# Moz_Mo_1_1.net
KiCad netlist of a schematic drawn in EAGLE
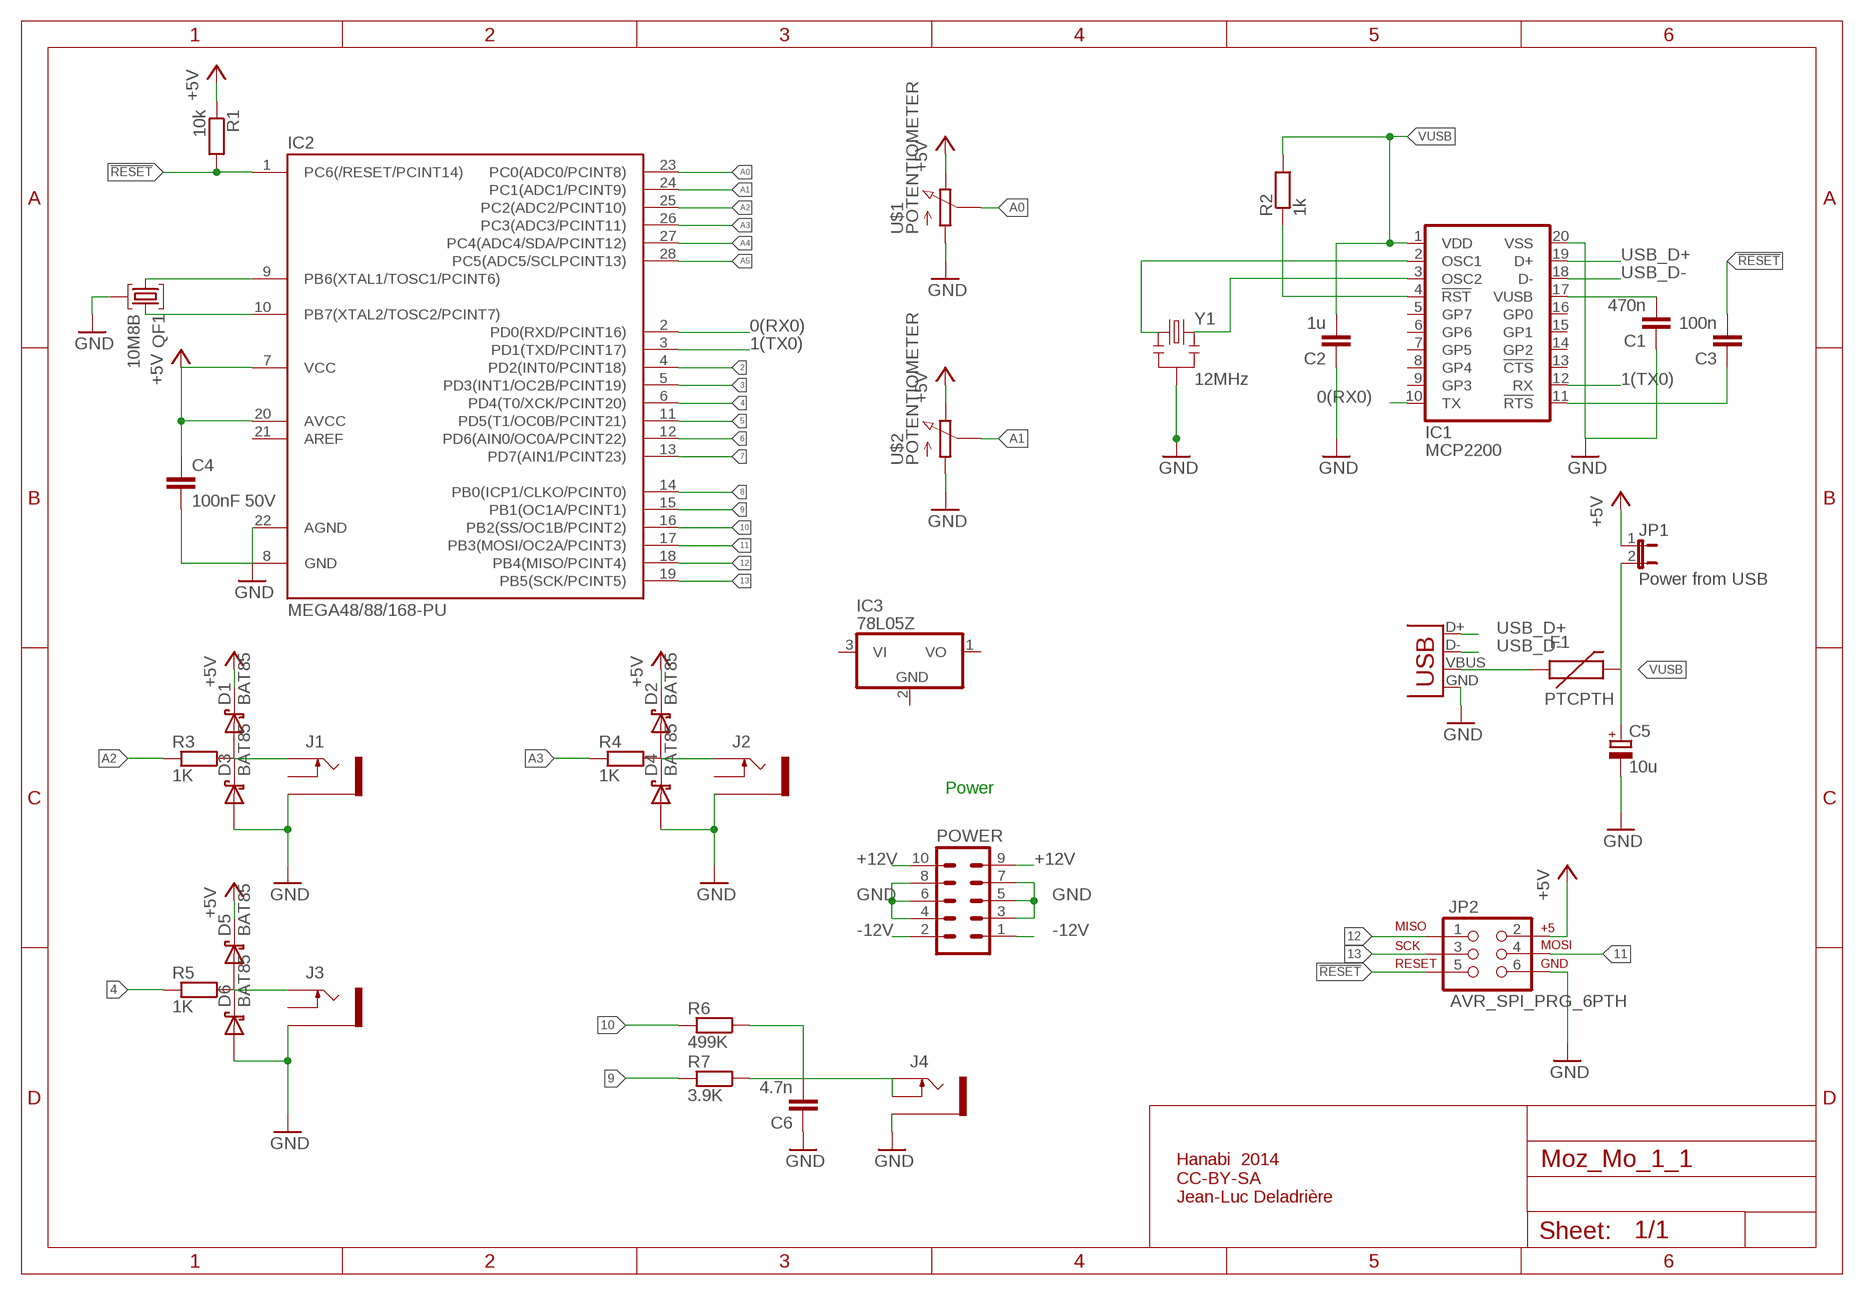
[diagram p0: schematic, sheet 1]

(export (version "E")
  (design (tool "Eeschema 10.0.6"))
  (components
    (comp (ref "C1")
      (value "470n")
      (footprint "eagle-import:CAP-PTH-SMALL")
      (libsource (lib "eagle-import") (part "CAPPTH"))
    )
    (comp (ref "C2")
      (value "1u")
      (footprint "eagle-import:CAP-PTH-5MM")
      (libsource (lib "eagle-import") (part "CAPPTH1"))
    )
    (comp (ref "C3")
      (value "100n")
      (footprint "eagle-import:CAP-PTH-SMALL")
      (libsource (lib "eagle-import") (part "CAPPTH"))
    )
    (comp (ref "C4")
      (value "100nF 50V")
      (footprint "eagle-import:C025-025X050")
      (libsource (lib "eagle-import") (part "C-EU025-025X050"))
    )
    (comp (ref "C5")
      (value "10u")
      (footprint "eagle-import:E2,5-7")
      (libsource (lib "eagle-import") (part "CPOL-EUE2.5-7"))
    )
    (comp (ref "C6")
      (value "4.7n")
      (footprint "eagle-import:CAP-PTH-SMALL")
      (libsource (lib "eagle-import") (part "CAPPTH"))
    )
    (comp (ref "D1")
      (value "BAT85")
      (footprint "eagle-import:DIODE-TH-0.4")
      (libsource (lib "eagle-import") (part "DIODE-SCHOTTKY"))
    )
    (comp (ref "D2")
      (value "BAT85")
      (footprint "eagle-import:DIODE-TH-0.4")
      (libsource (lib "eagle-import") (part "DIODE-SCHOTTKY"))
    )
    (comp (ref "D3")
      (value "BAT85")
      (footprint "eagle-import:DIODE-TH-0.4")
      (libsource (lib "eagle-import") (part "DIODE-SCHOTTKY"))
    )
    (comp (ref "D4")
      (value "BAT85")
      (footprint "eagle-import:DIODE-TH-0.4")
      (libsource (lib "eagle-import") (part "DIODE-SCHOTTKY"))
    )
    (comp (ref "D5")
      (value "BAT85")
      (footprint "eagle-import:DIODE-TH-0.4")
      (libsource (lib "eagle-import") (part "DIODE-SCHOTTKY"))
    )
    (comp (ref "D6")
      (value "BAT85")
      (footprint "eagle-import:DIODE-TH-0.4")
      (libsource (lib "eagle-import") (part "DIODE-SCHOTTKY"))
    )
    (comp (ref "F1")
      (value "PTCPTH")
      (footprint "eagle-import:PTC")
      (libsource (lib "eagle-import") (part "PTCPTH"))
    )
    (comp (ref "IC1")
      (value "MCP2200")
      (footprint "eagle-import:SO20")
      (libsource (lib "eagle-import") (part "MCP2200"))
    )
    (comp (ref "IC2")
      (value "MEGA48/88/168-PU")
      (footprint "eagle-import:DIL28-3")
      (libsource (lib "eagle-import") (part "MEGA48/88/168-PU"))
    )
    (comp (ref "IC3")
      (value "78L05Z")
      (footprint "eagle-import:TO92")
      (libsource (lib "eagle-import") (part "78ZL05"))
    )
    (comp (ref "J1")
      (value "1503_12")
      (footprint "eagle-import:1503_12")
      (libsource (lib "eagle-import") (part "1503_12"))
    )
    (comp (ref "J2")
      (value "1503_12")
      (footprint "eagle-import:1503_12")
      (libsource (lib "eagle-import") (part "1503_12"))
    )
    (comp (ref "J3")
      (value "1503_12")
      (footprint "eagle-import:1503_12")
      (libsource (lib "eagle-import") (part "1503_12"))
    )
    (comp (ref "J4")
      (value "1503_12")
      (footprint "eagle-import:1503_12")
      (libsource (lib "eagle-import") (part "1503_12"))
    )
    (comp (ref "JP1")
      (value "Power from USB")
      (footprint "eagle-import:JP1")
      (libsource (lib "eagle-import") (part "JP1E"))
    )
    (comp (ref "JP2")
      (value "AVR_SPI_PRG_6PTH")
      (footprint "eagle-import:2X3")
      (libsource (lib "eagle-import") (part "AVR_SPI_PRG_6PTH"))
    )
    (comp (ref "POWER")
      (value "10_PIN_HEADER")
      (footprint "eagle-import:MA05-2")
      (libsource (lib "eagle-import") (part "10_PIN_HEADER"))
    )
    (comp (ref "QF1")
      (value "10M8B")
      (footprint "eagle-import:HC49U")
      (fields (field (name "OC_FARNELL") "1448129"))
      (libsource (lib "eagle-import") (part "10MB8"))
    )
    (comp (ref "R1")
      (value "10k")
      (footprint "eagle-import:RES-AXIAL-0.4")
      (libsource (lib "eagle-import") (part "RESISTOR"))
    )
    (comp (ref "R2")
      (value "1k")
      (footprint "eagle-import:RES-AXIAL-0.4")
      (libsource (lib "eagle-import") (part "RESISTOR"))
    )
    (comp (ref "R3")
      (value "1K")
      (footprint "eagle-import:RES-AXIAL-0.4")
      (libsource (lib "eagle-import") (part "RESISTOR"))
    )
    (comp (ref "R4")
      (value "1K")
      (footprint "eagle-import:RES-AXIAL-0.4")
      (libsource (lib "eagle-import") (part "RESISTOR"))
    )
    (comp (ref "R5")
      (value "1K")
      (footprint "eagle-import:RES-AXIAL-0.4")
      (libsource (lib "eagle-import") (part "RESISTOR"))
    )
    (comp (ref "R6")
      (value "499K")
      (footprint "eagle-import:RES-AXIAL-0.4")
      (libsource (lib "eagle-import") (part "RESISTOR"))
    )
    (comp (ref "R7")
      (value "3.9K")
      (footprint "eagle-import:RES-AXIAL-0.4")
      (libsource (lib "eagle-import") (part "RESISTOR"))
    )
    (comp (ref "U$1")
      (value "POTENTIOMETER")
      (footprint "eagle-import:POTENTIOMETER")
      (libsource (lib "eagle-import") (part "POTENTIOMETER"))
    )
    (comp (ref "U$2")
      (value "POTENTIOMETER")
      (footprint "eagle-import:POTENTIOMETER")
      (libsource (lib "eagle-import") (part "POTENTIOMETER"))
    )
    (comp (ref "X1")
      (value "USB")
      (footprint "eagle-import:USB-B-PTH")
      (libsource (lib "eagle-import") (part "USBPTH"))
    )
    (comp (ref "Y1")
      (value "12MHz")
      (footprint "eagle-import:HC49U-V-RESONATOR")
      (libsource (lib "eagle-import") (part "CRYSTAL-RESONATOR"))
    )
  )
  (nets
    (net (code "1") (name "+5V") (class "Default")
      (node (ref "C4") (pin "1") (pinfunction "1_1") (pintype "passive"))
      (node (ref "D1") (pin "C") (pinfunction "C_C") (pintype "passive"))
      (node (ref "D2") (pin "C") (pinfunction "C_C") (pintype "passive"))
      (node (ref "D5") (pin "C") (pinfunction "C_C") (pintype "passive"))
      (node (ref "IC2") (pin "20") (pinfunction "AVCC_20") (pintype "passive"))
      (node (ref "IC2") (pin "7") (pinfunction "VCC_7") (pintype "power_in"))
      (node (ref "JP1") (pin "1") (pinfunction "1_1") (pintype "passive"))
      (node (ref "JP2") (pin "2") (pinfunction "2_2") (pintype "passive"))
      (node (ref "R1") (pin "P$1") (pinfunction "1_P$1") (pintype "passive"))
      (node (ref "U$1") (pin "P$1") (pinfunction "E_P$1") (pintype "passive"))
      (node (ref "U$2") (pin "P$1") (pinfunction "E_P$1") (pintype "passive"))
    )
    (net (code "2") (name "/+12V") (class "Default")
      (node (ref "POWER") (pin "10") (pinfunction "10_10") (pintype "passive"))
      (node (ref "POWER") (pin "9") (pinfunction "9_9") (pintype "passive"))
    )
    (net (code "3") (name "/-12V") (class "Default")
      (node (ref "POWER") (pin "1") (pinfunction "1_1") (pintype "passive"))
      (node (ref "POWER") (pin "2") (pinfunction "2_2") (pintype "passive"))
    )
    (net (code "4") (name "/0(RX0)") (class "Default")
      (node (ref "IC1") (pin "10") (pinfunction "TX_10") (pintype "bidirectional"))
      (node (ref "IC2") (pin "2") (pinfunction "PD0(RXD/PCINT16)_2") (pintype "bidirectional"))
    )
    (net (code "5") (name "/1(TX0)") (class "Default")
      (node (ref "IC1") (pin "12") (pinfunction "RX_12") (pintype "bidirectional"))
      (node (ref "IC2") (pin "3") (pinfunction "PD1(TXD/PCINT17)_3") (pintype "bidirectional"))
    )
    (net (code "6") (name "/USB_D+") (class "Default")
      (node (ref "IC1") (pin "19") (pinfunction "D+_19") (pintype "bidirectional"))
      (node (ref "X1") (pin "D+") (pinfunction "D+_D+") (pintype "bidirectional"))
    )
    (net (code "7") (name "/USB_D-") (class "Default")
      (node (ref "IC1") (pin "18") (pinfunction "D-_18") (pintype "bidirectional"))
      (node (ref "X1") (pin "D-") (pinfunction "D-_D-") (pintype "bidirectional"))
    )
    (net (code "8") (name "/~{RESET}") (class "Default")
      (node (ref "C3") (pin "2") (pinfunction "2_2") (pintype "passive"))
      (node (ref "IC2") (pin "1") (pinfunction "PC6(/RESET/PCINT14)_1") (pintype "bidirectional"))
      (node (ref "JP2") (pin "5") (pinfunction "5_5") (pintype "passive"))
      (node (ref "R1") (pin "P$2") (pinfunction "2_P$2") (pintype "passive"))
    )
    (net (code "9") (name "2") (class "Default")
      (node (ref "IC2") (pin "4") (pinfunction "PD2(INT0/PCINT18)_4") (pintype "bidirectional"))
    )
    (net (code "10") (name "3") (class "Default")
      (node (ref "IC2") (pin "5") (pinfunction "PD3(INT1/OC2B/PCINT19)_5") (pintype "bidirectional"))
    )
    (net (code "11") (name "4") (class "Default")
      (node (ref "IC2") (pin "6") (pinfunction "PD4(T0/XCK/PCINT20)_6") (pintype "bidirectional"))
      (node (ref "R5") (pin "P$1") (pinfunction "1_P$1") (pintype "passive"))
    )
    (net (code "12") (name "5") (class "Default")
      (node (ref "IC2") (pin "11") (pinfunction "PD5(T1/OC0B/PCINT21)_11") (pintype "bidirectional"))
    )
    (net (code "13") (name "6") (class "Default")
      (node (ref "IC2") (pin "12") (pinfunction "PD6(AIN0/OC0A/PCINT22)_12") (pintype "bidirectional"))
    )
    (net (code "14") (name "7") (class "Default")
      (node (ref "IC2") (pin "13") (pinfunction "PD7(AIN1/PCINT23)_13") (pintype "bidirectional"))
    )
    (net (code "15") (name "8") (class "Default")
      (node (ref "IC2") (pin "14") (pinfunction "PB0(ICP1/CLKO/PCINT0)_14") (pintype "bidirectional"))
    )
    (net (code "16") (name "9") (class "Default")
      (node (ref "IC2") (pin "15") (pinfunction "PB1(OC1A/PCINT1)_15") (pintype "bidirectional"))
      (node (ref "R7") (pin "P$1") (pinfunction "1_P$1") (pintype "passive"))
    )
    (net (code "17") (name "10") (class "Default")
      (node (ref "IC2") (pin "16") (pinfunction "PB2(SS/OC1B/PCINT2)_16") (pintype "bidirectional"))
      (node (ref "R6") (pin "P$1") (pinfunction "1_P$1") (pintype "passive"))
    )
    (net (code "18") (name "11") (class "Default")
      (node (ref "IC2") (pin "17") (pinfunction "PB3(MOSI/OC2A/PCINT3)_17") (pintype "bidirectional"))
      (node (ref "JP2") (pin "4") (pinfunction "4_4") (pintype "passive"))
    )
    (net (code "19") (name "12") (class "Default")
      (node (ref "IC2") (pin "18") (pinfunction "PB4(MISO/PCINT4)_18") (pintype "bidirectional"))
      (node (ref "JP2") (pin "1") (pinfunction "1_1") (pintype "passive"))
    )
    (net (code "20") (name "13") (class "Default")
      (node (ref "IC2") (pin "19") (pinfunction "PB5(SCK/PCINT5)_19") (pintype "bidirectional"))
      (node (ref "JP2") (pin "3") (pinfunction "3_3") (pintype "passive"))
    )
    (net (code "21") (name "A0") (class "Default")
      (node (ref "IC2") (pin "23") (pinfunction "PC0(ADC0/PCINT8)_23") (pintype "bidirectional"))
      (node (ref "U$1") (pin "P$2") (pinfunction "S_P$2") (pintype "passive"))
    )
    (net (code "22") (name "A1") (class "Default")
      (node (ref "IC2") (pin "24") (pinfunction "PC1(ADC1/PCINT9)_24") (pintype "bidirectional"))
      (node (ref "U$2") (pin "P$2") (pinfunction "S_P$2") (pintype "passive"))
    )
    (net (code "23") (name "A2") (class "Default")
      (node (ref "IC2") (pin "25") (pinfunction "PC2(ADC2/PCINT10)_25") (pintype "bidirectional"))
      (node (ref "R3") (pin "P$1") (pinfunction "1_P$1") (pintype "passive"))
    )
    (net (code "24") (name "A3") (class "Default")
      (node (ref "IC2") (pin "26") (pinfunction "PC3(ADC3/PCINT11)_26") (pintype "bidirectional"))
      (node (ref "R4") (pin "P$1") (pinfunction "1_P$1") (pintype "passive"))
    )
    (net (code "25") (name "A4") (class "Default")
      (node (ref "IC2") (pin "27") (pinfunction "PC4(ADC4/SDA/PCINT12)_27") (pintype "bidirectional"))
    )
    (net (code "26") (name "A5") (class "Default")
      (node (ref "IC2") (pin "28") (pinfunction "PC5(ADC5/SCLPCINT13)_28") (pintype "bidirectional"))
    )
    (net (code "27") (name "GND") (class "Default")
      (node (ref "C1") (pin "1") (pinfunction "1_1") (pintype "passive"))
      (node (ref "C2") (pin "1") (pinfunction "1_1") (pintype "passive"))
      (node (ref "C4") (pin "2") (pinfunction "2_2") (pintype "passive"))
      (node (ref "C5") (pin "-") (pinfunction "-_-") (pintype "passive"))
      (node (ref "C6") (pin "1") (pinfunction "1_1") (pintype "passive"))
      (node (ref "D3") (pin "A") (pinfunction "A_A") (pintype "passive"))
      (node (ref "D4") (pin "A") (pinfunction "A_A") (pintype "passive"))
      (node (ref "D6") (pin "A") (pinfunction "A_A") (pintype "passive"))
      (node (ref "IC1") (pin "20") (pinfunction "VSS_20") (pintype "power_in"))
      (node (ref "IC2") (pin "22") (pinfunction "AGND_22") (pintype "power_in"))
      (node (ref "IC2") (pin "8") (pinfunction "GND_8") (pintype "power_in"))
      (node (ref "J1") (pin "5") (pinfunction "1_5") (pintype "passive"))
      (node (ref "J2") (pin "5") (pinfunction "1_5") (pintype "passive"))
      (node (ref "J3") (pin "5") (pinfunction "1_5") (pintype "passive"))
      (node (ref "J4") (pin "5") (pinfunction "1_5") (pintype "passive"))
      (node (ref "JP2") (pin "6") (pinfunction "6_6") (pintype "passive"))
      (node (ref "POWER") (pin "3") (pinfunction "3_3") (pintype "passive"))
      (node (ref "POWER") (pin "4") (pinfunction "4_4") (pintype "passive"))
      (node (ref "POWER") (pin "5") (pinfunction "5_5") (pintype "passive"))
      (node (ref "POWER") (pin "6") (pinfunction "6_6") (pintype "passive"))
      (node (ref "POWER") (pin "7") (pinfunction "7_7") (pintype "passive"))
      (node (ref "POWER") (pin "8") (pinfunction "8_8") (pintype "passive"))
      (node (ref "QF1") (pin "2") (pinfunction "2_2") (pintype "passive"))
      (node (ref "U$1") (pin "P$3") (pinfunction "A_P$3") (pintype "passive"))
      (node (ref "U$2") (pin "P$3") (pinfunction "A_P$3") (pintype "passive"))
      (node (ref "X1") (pin "GND") (pinfunction "GND_GND") (pintype "bidirectional"))
      (node (ref "Y1") (pin "GND") (pinfunction "2_GND") (pintype "passive"))
    )
    (net (code "28") (name "Net-(F1-1)") (class "Default")
      (node (ref "F1") (pin "P$1") (pinfunction "1_P$1") (pintype "bidirectional"))
      (node (ref "X1") (pin "VBUS") (pinfunction "VBUS_VBUS") (pintype "bidirectional"))
    )
    (net (code "29") (name "Net-(IC1-OSC1)") (class "Default")
      (node (ref "IC1") (pin "2") (pinfunction "OSC1_2") (pintype "bidirectional"))
      (node (ref "Y1") (pin "1") (pinfunction "1_1") (pintype "passive"))
    )
    (net (code "30") (name "Net-(IC1-OSC2)") (class "Default")
      (node (ref "IC1") (pin "3") (pinfunction "OSC2_3") (pintype "bidirectional"))
      (node (ref "Y1") (pin "2") (pinfunction "3_2") (pintype "passive"))
    )
    (net (code "31") (name "Net-(IC1-VUSB)") (class "Default")
      (node (ref "C1") (pin "2") (pinfunction "2_2") (pintype "passive"))
      (node (ref "IC1") (pin "17") (pinfunction "VUSB_17") (pintype "bidirectional"))
    )
    (net (code "32") (name "Net-(IC1-~{RST})") (class "Default")
      (node (ref "IC1") (pin "4") (pinfunction "~{RST}_4") (pintype "bidirectional"))
      (node (ref "R2") (pin "P$1") (pinfunction "1_P$1") (pintype "passive"))
    )
    (net (code "33") (name "Net-(IC1-~{RTS})") (class "Default")
      (node (ref "C3") (pin "1") (pinfunction "1_1") (pintype "passive"))
      (node (ref "IC1") (pin "11") (pinfunction "~{RTS}_11") (pintype "bidirectional"))
    )
    (net (code "34") (name "Net-(IC2-PB6(XTAL1{slash}TOSC1{slash}PCINT6))") (class "Default")
      (node (ref "IC2") (pin "9") (pinfunction "PB6(XTAL1/TOSC1/PCINT6)_9") (pintype "bidirectional"))
      (node (ref "QF1") (pin "1") (pinfunction "1_1") (pintype "passive"))
    )
    (net (code "35") (name "Net-(IC2-PB7(XTAL2{slash}TOSC2{slash}PCINT7))") (class "Default")
      (node (ref "IC2") (pin "10") (pinfunction "PB7(XTAL2/TOSC2/PCINT7)_10") (pintype "bidirectional"))
      (node (ref "QF1") (pin "3") (pinfunction "3_3") (pintype "passive"))
    )
    (net (code "36") (name "Net-(J1-2)") (class "Default")
      (node (ref "D1") (pin "A") (pinfunction "A_A") (pintype "passive"))
      (node (ref "D3") (pin "C") (pinfunction "C_C") (pintype "passive"))
      (node (ref "J1") (pin "3") (pinfunction "2_3") (pintype "passive"))
      (node (ref "R3") (pin "P$2") (pinfunction "2_P$2") (pintype "passive"))
    )
    (net (code "37") (name "Net-(J2-2)") (class "Default")
      (node (ref "D2") (pin "A") (pinfunction "A_A") (pintype "passive"))
      (node (ref "D4") (pin "C") (pinfunction "C_C") (pintype "passive"))
      (node (ref "J2") (pin "3") (pinfunction "2_3") (pintype "passive"))
      (node (ref "R4") (pin "P$2") (pinfunction "2_P$2") (pintype "passive"))
    )
    (net (code "38") (name "Net-(J3-2)") (class "Default")
      (node (ref "D5") (pin "A") (pinfunction "A_A") (pintype "passive"))
      (node (ref "D6") (pin "C") (pinfunction "C_C") (pintype "passive"))
      (node (ref "J3") (pin "3") (pinfunction "2_3") (pintype "passive"))
      (node (ref "R5") (pin "P$2") (pinfunction "2_P$2") (pintype "passive"))
    )
    (net (code "39") (name "Net-(J4-2)") (class "Default")
      (node (ref "C6") (pin "2") (pinfunction "2_2") (pintype "passive"))
      (node (ref "J4") (pin "3") (pinfunction "2_3") (pintype "passive"))
      (node (ref "J4") (pin "4") (pinfunction "3_4") (pintype "passive"))
      (node (ref "R6") (pin "P$2") (pinfunction "2_P$2") (pintype "passive"))
      (node (ref "R7") (pin "P$2") (pinfunction "2_P$2") (pintype "passive"))
    )
    (net (code "40") (name "VUSB") (class "Default")
      (node (ref "C2") (pin "2") (pinfunction "2_2") (pintype "passive"))
      (node (ref "C5") (pin "+") (pinfunction "+_+") (pintype "passive"))
      (node (ref "F1") (pin "P$2") (pinfunction "2_P$2") (pintype "bidirectional"))
      (node (ref "IC1") (pin "1") (pinfunction "VDD_1") (pintype "power_in"))
      (node (ref "JP1") (pin "2") (pinfunction "2_2") (pintype "passive"))
      (node (ref "R2") (pin "P$2") (pinfunction "2_P$2") (pintype "passive"))
    )
    (net (code "41") (name "unconnected-(IC1-GP0-Pad16)") (class "Default")
      (node (ref "IC1") (pin "16") (pinfunction "GP0_16") (pintype "bidirectional"))
    )
    (net (code "42") (name "unconnected-(IC1-GP1-Pad15)") (class "Default")
      (node (ref "IC1") (pin "15") (pinfunction "GP1_15") (pintype "bidirectional"))
    )
    (net (code "43") (name "unconnected-(IC1-GP2-Pad14)") (class "Default")
      (node (ref "IC1") (pin "14") (pinfunction "GP2_14") (pintype "bidirectional"))
    )
    (net (code "44") (name "unconnected-(IC1-GP3-Pad9)") (class "Default")
      (node (ref "IC1") (pin "9") (pinfunction "GP3_9") (pintype "bidirectional"))
    )
    (net (code "45") (name "unconnected-(IC1-GP4-Pad8)") (class "Default")
      (node (ref "IC1") (pin "8") (pinfunction "GP4_8") (pintype "bidirectional"))
    )
    (net (code "46") (name "unconnected-(IC1-GP5-Pad7)") (class "Default")
      (node (ref "IC1") (pin "7") (pinfunction "GP5_7") (pintype "bidirectional"))
    )
    (net (code "47") (name "unconnected-(IC1-GP6-Pad6)") (class "Default")
      (node (ref "IC1") (pin "6") (pinfunction "GP6_6") (pintype "bidirectional"))
    )
    (net (code "48") (name "unconnected-(IC1-GP7-Pad5)") (class "Default")
      (node (ref "IC1") (pin "5") (pinfunction "GP7_5") (pintype "bidirectional"))
    )
    (net (code "49") (name "unconnected-(IC1-~{CTS}-Pad13)") (class "Default")
      (node (ref "IC1") (pin "13") (pinfunction "~{CTS}_13") (pintype "bidirectional"))
    )
    (net (code "50") (name "unconnected-(IC2-AREF-Pad21)") (class "Default")
      (node (ref "IC2") (pin "21") (pinfunction "AREF_21") (pintype "passive"))
    )
    (net (code "51") (name "unconnected-(IC3-GND-Pad2)") (class "Default")
      (node (ref "IC3") (pin "2") (pinfunction "GND_2") (pintype "passive"))
    )
    (net (code "52") (name "unconnected-(IC3-VI-Pad3)") (class "Default")
      (node (ref "IC3") (pin "3") (pinfunction "VI_3") (pintype "input"))
    )
    (net (code "53") (name "unconnected-(IC3-VO-Pad1)") (class "Default")
      (node (ref "IC3") (pin "1") (pinfunction "VO_1") (pintype "passive"))
    )
    (net (code "54") (name "unconnected-(J1-3-Pad4)") (class "Default")
      (node (ref "J1") (pin "4") (pinfunction "3_4") (pintype "passive"))
    )
    (net (code "55") (name "unconnected-(J2-3-Pad4)") (class "Default")
      (node (ref "J2") (pin "4") (pinfunction "3_4") (pintype "passive"))
    )
    (net (code "56") (name "unconnected-(J3-3-Pad4)") (class "Default")
      (node (ref "J3") (pin "4") (pinfunction "3_4") (pintype "passive"))
    )
  )
)
